# PineapplePi-F1.net
KiCad netlist of a schematic drawn in Altium Designer
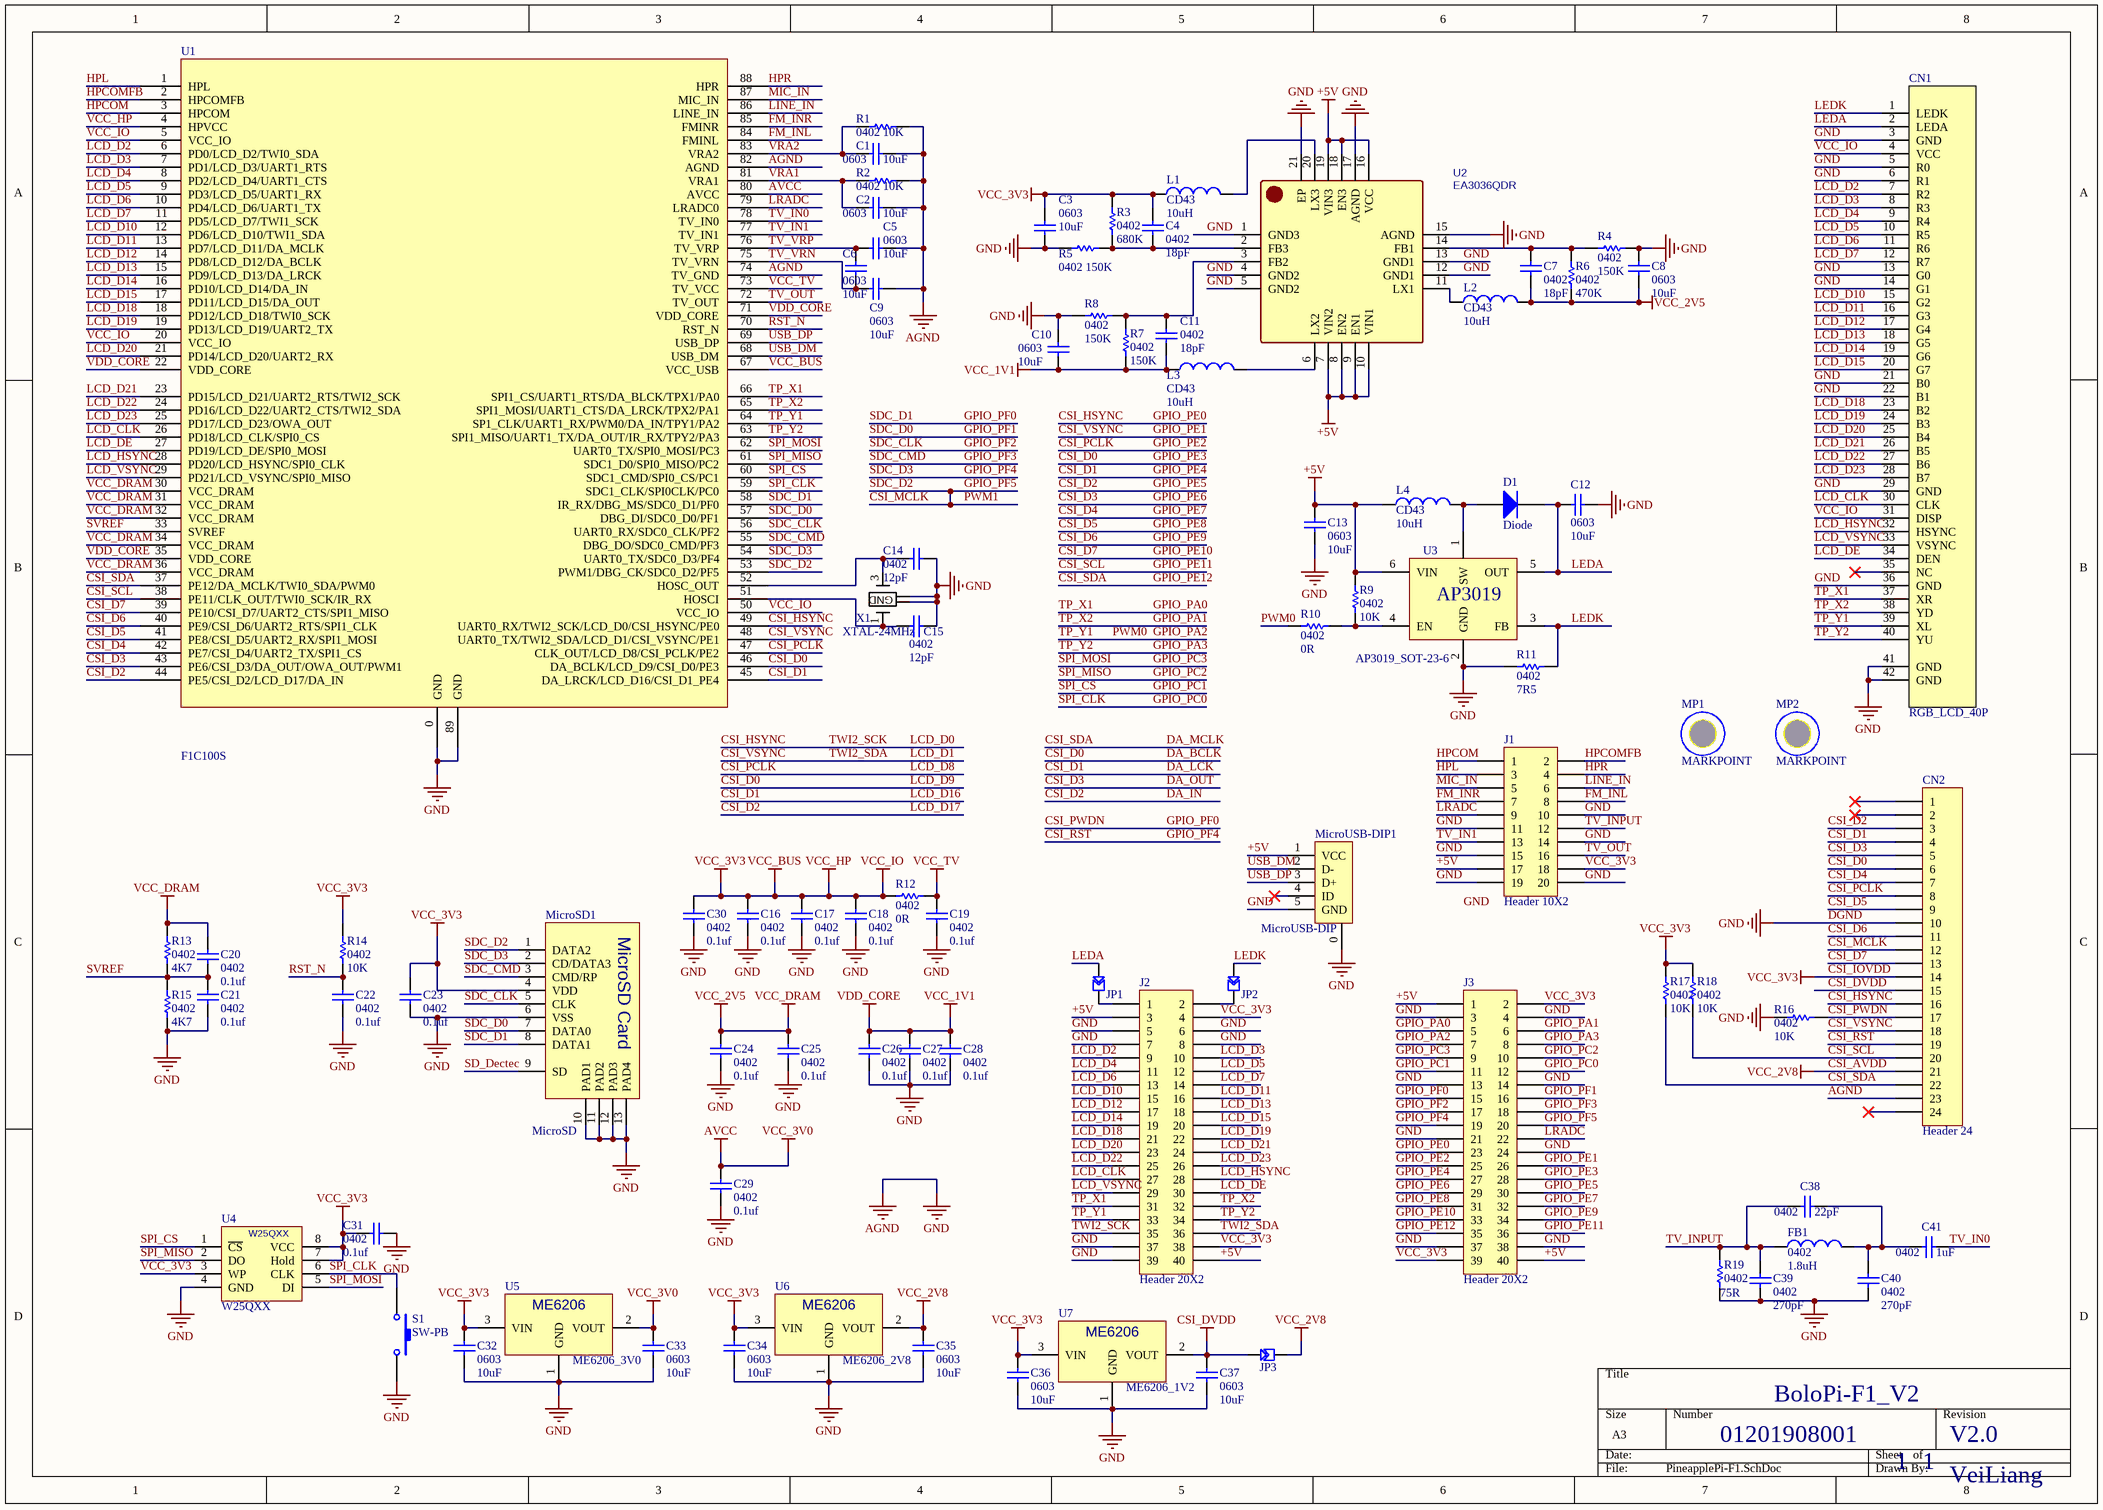
[diagram p0: PineapplePi-F1.SchDoc]

(export (version "E")
  (design (tool "Eeschema 10.0.6"))
  (components
    (comp (ref "C1")
      (value "0603")
      (footprint "0603AC")
      (description "Capacitor")
      (fields (field (name "ALTIUM_VALUE") "10uF") (field (name "PUBLISHER") "Altium Limited"))
      (libsource (lib "Miscellaneous Devices") (part "Cap"))
    )
    (comp (ref "C2")
      (value "0603")
      (footprint "0603AC")
      (description "Capacitor")
      (fields (field (name "ALTIUM_VALUE") "10uF") (field (name "PUBLISHER") "Altium Limited"))
      (libsource (lib "Miscellaneous Devices") (part "Cap"))
    )
    (comp (ref "C3")
      (value "0603")
      (footprint "0603AC")
      (description "Capacitor")
      (fields (field (name "ALTIUM_VALUE") "10uF") (field (name "PUBLISHER") "Altium Limited"))
      (libsource (lib "Miscellaneous Devices") (part "Cap"))
    )
    (comp (ref "C4")
      (value "0402")
      (footprint "0402AC")
      (description "Capacitor")
      (fields (field (name "ALTIUM_VALUE") "18pF") (field (name "PUBLISHER") "Altium Limited"))
      (libsource (lib "Miscellaneous Devices") (part "Cap"))
    )
    (comp (ref "C5")
      (value "0603")
      (footprint "0603AC")
      (description "Capacitor")
      (fields (field (name "ALTIUM_VALUE") "10uF") (field (name "PUBLISHER") "Altium Limited"))
      (libsource (lib "Miscellaneous Devices") (part "Cap"))
    )
    (comp (ref "C6")
      (value "0603")
      (footprint "0603AC")
      (description "Capacitor")
      (fields (field (name "ALTIUM_VALUE") "10uF") (field (name "PUBLISHER") "Altium Limited"))
      (libsource (lib "Miscellaneous Devices") (part "Cap"))
    )
    (comp (ref "C7")
      (value "0402")
      (footprint "0402AC")
      (description "Capacitor")
      (fields (field (name "ALTIUM_VALUE") "18pF") (field (name "PUBLISHER") "Altium Limited"))
      (libsource (lib "Miscellaneous Devices") (part "Cap"))
    )
    (comp (ref "C8")
      (value "0603")
      (footprint "0603AC")
      (description "Capacitor")
      (fields (field (name "ALTIUM_VALUE") "10uF") (field (name "PUBLISHER") "Altium Limited"))
      (libsource (lib "Miscellaneous Devices") (part "Cap"))
    )
    (comp (ref "C9")
      (value "0603")
      (footprint "0603AC")
      (description "Capacitor")
      (fields (field (name "ALTIUM_VALUE") "10uF") (field (name "PUBLISHER") "Altium Limited"))
      (libsource (lib "Miscellaneous Devices") (part "Cap"))
    )
    (comp (ref "C10")
      (value "0603")
      (footprint "0603AC")
      (description "Capacitor")
      (fields (field (name "ALTIUM_VALUE") "10uF") (field (name "PUBLISHER") "Altium Limited"))
      (libsource (lib "Miscellaneous Devices") (part "Cap"))
    )
    (comp (ref "C11")
      (value "0402")
      (footprint "0402AC")
      (description "Capacitor")
      (fields (field (name "ALTIUM_VALUE") "18pF") (field (name "PUBLISHER") "Altium Limited"))
      (libsource (lib "Miscellaneous Devices") (part "Cap"))
    )
    (comp (ref "C12")
      (value "0603")
      (footprint "0603AC")
      (description "Capacitor")
      (fields (field (name "ALTIUM_VALUE") "10uF") (field (name "PUBLISHER") "Altium Limited"))
      (libsource (lib "Miscellaneous Devices") (part "Cap"))
    )
    (comp (ref "C13")
      (value "0603")
      (footprint "0603AC")
      (description "Capacitor")
      (fields (field (name "ALTIUM_VALUE") "10uF") (field (name "PUBLISHER") "Altium Limited"))
      (libsource (lib "Miscellaneous Devices") (part "Cap"))
    )
    (comp (ref "C14")
      (value "0402")
      (footprint "0402AC")
      (description "Capacitor")
      (fields (field (name "ALTIUM_VALUE") "12pF") (field (name "PUBLISHER") "Altium Limited"))
      (libsource (lib "Miscellaneous Devices") (part "Cap"))
    )
    (comp (ref "C15")
      (value "0402")
      (footprint "0402AC")
      (description "Capacitor")
      (fields (field (name "ALTIUM_VALUE") "12pF") (field (name "PUBLISHER") "Altium Limited"))
      (libsource (lib "Miscellaneous Devices") (part "Cap"))
    )
    (comp (ref "C16")
      (value "0402")
      (footprint "0402AC")
      (description "Capacitor")
      (fields (field (name "ALTIUM_VALUE") "0.1uf") (field (name "PUBLISHER") "Altium Limited"))
      (libsource (lib "Miscellaneous Devices") (part "Cap"))
    )
    (comp (ref "C17")
      (value "0402")
      (footprint "0402AC")
      (description "Capacitor")
      (fields (field (name "ALTIUM_VALUE") "0.1uf") (field (name "PUBLISHER") "Altium Limited"))
      (libsource (lib "Miscellaneous Devices") (part "Cap"))
    )
    (comp (ref "C18")
      (value "0402")
      (footprint "0402AC")
      (description "Capacitor")
      (fields (field (name "ALTIUM_VALUE") "0.1uf") (field (name "PUBLISHER") "Altium Limited"))
      (libsource (lib "Miscellaneous Devices") (part "Cap"))
    )
    (comp (ref "C19")
      (value "0402")
      (footprint "0402AC")
      (description "Capacitor")
      (fields (field (name "ALTIUM_VALUE") "0.1uf") (field (name "PUBLISHER") "Altium Limited"))
      (libsource (lib "Miscellaneous Devices") (part "Cap"))
    )
    (comp (ref "C20")
      (value "0402")
      (footprint "0402AC")
      (description "Capacitor")
      (fields (field (name "ALTIUM_VALUE") "0.1uf") (field (name "PUBLISHER") "Altium Limited"))
      (libsource (lib "Miscellaneous Devices") (part "Cap"))
    )
    (comp (ref "C21")
      (value "0402")
      (footprint "0402AC")
      (description "Capacitor")
      (fields (field (name "ALTIUM_VALUE") "0.1uf") (field (name "PUBLISHER") "Altium Limited"))
      (libsource (lib "Miscellaneous Devices") (part "Cap"))
    )
    (comp (ref "C22")
      (value "0402")
      (footprint "0402AC")
      (description "Capacitor")
      (fields (field (name "ALTIUM_VALUE") "0.1uf") (field (name "PUBLISHER") "Altium Limited"))
      (libsource (lib "Miscellaneous Devices") (part "Cap"))
    )
    (comp (ref "C23")
      (value "0402")
      (footprint "0402AC")
      (description "Capacitor")
      (fields (field (name "ALTIUM_VALUE") "0.1uf") (field (name "PUBLISHER") "Altium Limited"))
      (libsource (lib "Miscellaneous Devices") (part "Cap"))
    )
    (comp (ref "C24")
      (value "0402")
      (footprint "0402AC")
      (description "Capacitor")
      (fields (field (name "ALTIUM_VALUE") "0.1uf") (field (name "PUBLISHER") "Altium Limited"))
      (libsource (lib "Miscellaneous Devices") (part "Cap"))
    )
    (comp (ref "C25")
      (value "0402")
      (footprint "0402AC")
      (description "Capacitor")
      (fields (field (name "ALTIUM_VALUE") "0.1uf") (field (name "PUBLISHER") "Altium Limited"))
      (libsource (lib "Miscellaneous Devices") (part "Cap"))
    )
    (comp (ref "C26")
      (value "0402")
      (footprint "0402AC")
      (description "Capacitor")
      (fields (field (name "ALTIUM_VALUE") "0.1uf") (field (name "PUBLISHER") "Altium Limited"))
      (libsource (lib "Miscellaneous Devices") (part "Cap"))
    )
    (comp (ref "C27")
      (value "0402")
      (footprint "0402AC")
      (description "Capacitor")
      (fields (field (name "ALTIUM_VALUE") "0.1uf") (field (name "PUBLISHER") "Altium Limited"))
      (libsource (lib "Miscellaneous Devices") (part "Cap"))
    )
    (comp (ref "C28")
      (value "0402")
      (footprint "0402AC")
      (description "Capacitor")
      (fields (field (name "ALTIUM_VALUE") "0.1uf") (field (name "PUBLISHER") "Altium Limited"))
      (libsource (lib "Miscellaneous Devices") (part "Cap"))
    )
    (comp (ref "C29")
      (value "0402")
      (footprint "0402AC")
      (description "Capacitor")
      (fields (field (name "ALTIUM_VALUE") "0.1uf") (field (name "PUBLISHER") "Altium Limited"))
      (libsource (lib "Miscellaneous Devices") (part "Cap"))
    )
    (comp (ref "C30")
      (value "0402")
      (footprint "0402AC")
      (description "Capacitor")
      (fields (field (name "ALTIUM_VALUE") "0.1uf") (field (name "PUBLISHER") "Altium Limited"))
      (libsource (lib "Miscellaneous Devices") (part "Cap"))
    )
    (comp (ref "C31")
      (value "0402")
      (footprint "0402AC")
      (description "Capacitor")
      (fields (field (name "ALTIUM_VALUE") "0.1uf") (field (name "PUBLISHER") "Altium Limited"))
      (libsource (lib "Miscellaneous Devices") (part "Cap"))
    )
    (comp (ref "C32")
      (value "0603")
      (footprint "0603AC")
      (description "Capacitor")
      (fields (field (name "ALTIUM_VALUE") "10uF") (field (name "PUBLISHER") "Altium Limited"))
      (libsource (lib "Miscellaneous Devices") (part "Cap"))
    )
    (comp (ref "C33")
      (value "0603")
      (footprint "0603AC")
      (description "Capacitor")
      (fields (field (name "ALTIUM_VALUE") "10uF") (field (name "PUBLISHER") "Altium Limited"))
      (libsource (lib "Miscellaneous Devices") (part "Cap"))
    )
    (comp (ref "C34")
      (value "0603")
      (footprint "0603AC")
      (description "Capacitor")
      (fields (field (name "ALTIUM_VALUE") "10uF") (field (name "PUBLISHER") "Altium Limited"))
      (libsource (lib "Miscellaneous Devices") (part "Cap"))
    )
    (comp (ref "C35")
      (value "0603")
      (footprint "0603AC")
      (description "Capacitor")
      (fields (field (name "ALTIUM_VALUE") "10uF") (field (name "PUBLISHER") "Altium Limited"))
      (libsource (lib "Miscellaneous Devices") (part "Cap"))
    )
    (comp (ref "C36")
      (value "0603")
      (footprint "0603AC")
      (description "Capacitor")
      (fields (field (name "ALTIUM_VALUE") "10uF") (field (name "PUBLISHER") "Altium Limited"))
      (libsource (lib "Miscellaneous Devices") (part "Cap"))
    )
    (comp (ref "C37")
      (value "0603")
      (footprint "0603AC")
      (description "Capacitor")
      (fields (field (name "ALTIUM_VALUE") "10uF") (field (name "PUBLISHER") "Altium Limited"))
      (libsource (lib "Miscellaneous Devices") (part "Cap"))
    )
    (comp (ref "C38")
      (value "0402")
      (footprint "0402AC")
      (description "Capacitor")
      (fields (field (name "ALTIUM_VALUE") "22pF") (field (name "PUBLISHER") "Altium Limited"))
      (libsource (lib "Miscellaneous Devices") (part "Cap"))
    )
    (comp (ref "C39")
      (value "0402")
      (footprint "0402AC")
      (description "Capacitor")
      (fields (field (name "ALTIUM_VALUE") "270pF") (field (name "PUBLISHER") "Altium Limited"))
      (libsource (lib "Miscellaneous Devices") (part "Cap"))
    )
    (comp (ref "C40")
      (value "0402")
      (footprint "0402AC")
      (description "Capacitor")
      (fields (field (name "ALTIUM_VALUE") "270pF") (field (name "PUBLISHER") "Altium Limited"))
      (libsource (lib "Miscellaneous Devices") (part "Cap"))
    )
    (comp (ref "C41")
      (value "0402")
      (footprint "0402AC")
      (description "Capacitor")
      (fields (field (name "ALTIUM_VALUE") "1uF") (field (name "PUBLISHER") "Altium Limited"))
      (libsource (lib "Miscellaneous Devices") (part "Cap"))
    )
    (comp (ref "CN1")
      (value "RGB_LCD_40P")
      (footprint "FH19C-40S-0.5SH")
      (libsource (lib "7426SCH") (part "RGB_LCD_40P"))
    )
    (comp (ref "CN2")
      (value "Header 24")
      (footprint "FH19C-24S-0.5SH")
      (description "Header, 24-Pin")
      (fields (field (name "PUBLISHER") "Altium Limited"))
      (libsource (lib "Miscellaneous Connectors") (part "Header 24"))
    )
    (comp (ref "D1")
      (value "Diode")
      (footprint "SOD123")
      (description "Default Diode")
      (fields (field (name "PUBLISHER") "Altium Limited"))
      (libsource (lib "Miscellaneous Devices") (part "Diode"))
    )
    (comp (ref "FB1")
      (value "0402")
      (footprint "0402AR")
      (description "CD43")
      (fields (field (name "ALTIUM_VALUE") "1.8uH") (field (name "PUBLISHER") "Altium Limited"))
      (libsource (lib "Miscellaneous Devices") (part "Inductor"))
    )
    (comp (ref "J1")
      (value "Header 10X2")
      (footprint "Headers:HDR2X10-2.0mm")
      (description "Header, 10-Pin, Dual row")
      (fields (field (name "PUBLISHER") "Altium Limited"))
      (libsource (lib "Miscellaneous Connectors") (part "Header 10X2"))
    )
    (comp (ref "J2")
      (value "Header 20X2")
      (footprint "headers:HDR2X20")
      (description "Header, 20-Pin, Dual row")
      (fields (field (name "PUBLISHER") "Altium Limited"))
      (libsource (lib "Miscellaneous Connectors") (part "Header 20X2"))
    )
    (comp (ref "J3")
      (value "Header 20X2")
      (footprint "headers:HDR2X20")
      (description "Header, 20-Pin, Dual row")
      (fields (field (name "PUBLISHER") "Altium Limited"))
      (libsource (lib "Miscellaneous Connectors") (part "Header 20X2"))
    )
    (comp (ref "JP1") (value "SW-PAD-2") (footprint "SW-PAD-2") (libsource (lib "7426SCH") (part "SW-PAD-2")))
    (comp (ref "JP2") (value "SW-PAD-2") (footprint "SW-PAD-2") (libsource (lib "7426SCH") (part "SW-PAD-2")))
    (comp (ref "JP3") (value "SW-PAD-2") (footprint "SW-PAD-2") (libsource (lib "7426SCH") (part "SW-PAD-2")))
    (comp (ref "L1")
      (value "CD43")
      (footprint "2520")
      (fields (field (name "ALTIUM_VALUE") "10uH") (field (name "PUBLISHER") "Altium Limited"))
      (libsource (lib "Miscellaneous Devices") (part "Inductor"))
    )
    (comp (ref "L2")
      (value "CD43")
      (footprint "2520")
      (fields (field (name "ALTIUM_VALUE") "10uH") (field (name "PUBLISHER") "Altium Limited"))
      (libsource (lib "Miscellaneous Devices") (part "Inductor"))
    )
    (comp (ref "L3")
      (value "CD43")
      (footprint "2520")
      (fields (field (name "ALTIUM_VALUE") "10uH") (field (name "PUBLISHER") "Altium Limited"))
      (libsource (lib "Miscellaneous Devices") (part "Inductor"))
    )
    (comp (ref "L4")
      (value "CD43")
      (footprint "2520")
      (fields (field (name "ALTIUM_VALUE") "10uH") (field (name "PUBLISHER") "Altium Limited"))
      (libsource (lib "Miscellaneous Devices") (part "Inductor"))
    )
    (comp (ref "MicroSD1")
      (value "MicroSD")
      (footprint "MicroSD")
      (libsource (lib "7426SCH") (part "MicroSD"))
    )
    (comp (ref "MicroUSB-DIP1")
      (value "MicroUSB-DIP")
      (footprint "MICRO_USB_DIP")
      (libsource (lib "7426SCH") (part "MicroUSB-DIP"))
    )
    (comp (ref "MP1")
      (value "MARKPOINT")
      (footprint "MARKPOINT")
      (libsource (lib "7426SCH") (part "MARKPOINT"))
    )
    (comp (ref "MP2")
      (value "MARKPOINT")
      (footprint "MARKPOINT")
      (libsource (lib "7426SCH") (part "MARKPOINT"))
    )
    (comp (ref "R1")
      (value "0402")
      (footprint "0402AR")
      (description "Resistor")
      (fields (field (name "ALTIUM_VALUE") "10K") (field (name "PUBLISHER") "Altium Limited"))
      (libsource (lib "Miscellaneous Devices") (part "Res1"))
    )
    (comp (ref "R2")
      (value "0402")
      (footprint "0402AR")
      (description "Resistor")
      (fields (field (name "ALTIUM_VALUE") "10K") (field (name "PUBLISHER") "Altium Limited"))
      (libsource (lib "Miscellaneous Devices") (part "Res1"))
    )
    (comp (ref "R3")
      (value "0402")
      (footprint "0402AR")
      (fields (field (name "ALTIUM_VALUE") "680K") (field (name "PUBLISHER") "Altium Limited"))
      (libsource (lib "Miscellaneous Devices") (part "Res1"))
    )
    (comp (ref "R4")
      (value "0402")
      (footprint "0402AR")
      (description "Resistor")
      (fields (field (name "ALTIUM_VALUE") "150K") (field (name "PUBLISHER") "Altium Limited"))
      (libsource (lib "Miscellaneous Devices") (part "Res1"))
    )
    (comp (ref "R5")
      (value "0402")
      (footprint "0402AR")
      (description "Resistor")
      (fields (field (name "ALTIUM_VALUE") "150K") (field (name "PUBLISHER") "Altium Limited"))
      (libsource (lib "Miscellaneous Devices") (part "Res1"))
    )
    (comp (ref "R6")
      (value "0402")
      (footprint "0402AR")
      (fields (field (name "ALTIUM_VALUE") "470K") (field (name "PUBLISHER") "Altium Limited"))
      (libsource (lib "Miscellaneous Devices") (part "Res1"))
    )
    (comp (ref "R7")
      (value "0402")
      (footprint "0402AR")
      (fields (field (name "ALTIUM_VALUE") "150K") (field (name "PUBLISHER") "Altium Limited"))
      (libsource (lib "Miscellaneous Devices") (part "Res1"))
    )
    (comp (ref "R8")
      (value "0402")
      (footprint "0402AR")
      (fields (field (name "ALTIUM_VALUE") "150K") (field (name "PUBLISHER") "Altium Limited"))
      (libsource (lib "Miscellaneous Devices") (part "Res1"))
    )
    (comp (ref "R9")
      (value "0402")
      (footprint "0402AR")
      (fields (field (name "ALTIUM_VALUE") "10K") (field (name "PUBLISHER") "Altium Limited"))
      (libsource (lib "Miscellaneous Devices") (part "Res1"))
    )
    (comp (ref "R10")
      (value "0402")
      (footprint "0402AR")
      (fields (field (name "ALTIUM_VALUE") "0R") (field (name "PUBLISHER") "Altium Limited"))
      (libsource (lib "Miscellaneous Devices") (part "Res1"))
    )
    (comp (ref "R11")
      (value "0402")
      (footprint "0402AR")
      (fields (field (name "ALTIUM_VALUE") "7R5") (field (name "PUBLISHER") "Altium Limited"))
      (libsource (lib "Miscellaneous Devices") (part "Res1"))
    )
    (comp (ref "R12")
      (value "0402")
      (footprint "0402AR")
      (fields (field (name "ALTIUM_VALUE") "0R") (field (name "PUBLISHER") "Altium Limited"))
      (libsource (lib "Miscellaneous Devices") (part "Res1"))
    )
    (comp (ref "R13")
      (value "0402")
      (footprint "0402AR")
      (fields (field (name "ALTIUM_VALUE") "4K7") (field (name "PUBLISHER") "Altium Limited"))
      (libsource (lib "Miscellaneous Devices") (part "Res1"))
    )
    (comp (ref "R14")
      (value "0402")
      (footprint "0402AR")
      (fields (field (name "ALTIUM_VALUE") "10K") (field (name "PUBLISHER") "Altium Limited"))
      (libsource (lib "Miscellaneous Devices") (part "Res1"))
    )
    (comp (ref "R15")
      (value "0402")
      (footprint "0402AR")
      (fields (field (name "ALTIUM_VALUE") "4K7") (field (name "PUBLISHER") "Altium Limited"))
      (libsource (lib "Miscellaneous Devices") (part "Res1"))
    )
    (comp (ref "R16")
      (value "0402")
      (footprint "0402AR")
      (fields (field (name "ALTIUM_VALUE") "10K") (field (name "PUBLISHER") "Altium Limited"))
      (libsource (lib "Miscellaneous Devices") (part "Res1"))
    )
    (comp (ref "R17")
      (value "0402")
      (footprint "0402AR")
      (fields (field (name "ALTIUM_VALUE") "10K") (field (name "PUBLISHER") "Altium Limited"))
      (libsource (lib "Miscellaneous Devices") (part "Res1"))
    )
    (comp (ref "R18")
      (value "0402")
      (footprint "0402AR")
      (fields (field (name "ALTIUM_VALUE") "10K") (field (name "PUBLISHER") "Altium Limited"))
      (libsource (lib "Miscellaneous Devices") (part "Res1"))
    )
    (comp (ref "R19")
      (value "0402")
      (footprint "0402AR")
      (description "Resistor")
      (fields (field (name "ALTIUM_VALUE") "75R") (field (name "PUBLISHER") "Altium Limited"))
      (libsource (lib "Miscellaneous Devices") (part "Res1"))
    )
    (comp (ref "S1")
      (value "SW-PB")
      (footprint "SW-SMD1")
      (description "Switch")
      (fields (field (name "PUBLISHER") "Altium Limited"))
      (libsource (lib "Miscellaneous Devices") (part "SW-PB"))
    )
    (comp (ref "U1") (value "F1C100S") (footprint "QFN88-10X10") (libsource (lib "7426SCH") (part "F1C100S")))
    (comp (ref "U2")
      (value "EA3036QDR")
      (footprint "QFN20-3x3-0.4")
      (fields (field (name "BOM_SUPPLIER PART") "C111587"))
      (libsource (lib "IC") (part "EA3036QDR"))
    )
    (comp (ref "U3") (value "AP3019_SOT-23-6") (footprint "SOT23-6") (libsource (lib "IC") (part "AP3019")))
    (comp (ref "U4") (value "W25QXX") (footprint "IC:SO-8M") (libsource (lib "IC") (part "W25QXX")))
    (comp (ref "U5") (value "ME6206_3V0") (footprint "SOT-23") (libsource (lib "IC") (part "ME6206")))
    (comp (ref "U6") (value "ME6206_2V8") (footprint "SOT-23") (libsource (lib "IC") (part "ME6206")))
    (comp (ref "U7") (value "ME6206_1V2") (footprint "SOT-23") (libsource (lib "IC") (part "ME6206")))
    (comp (ref "X1")
      (value "XTAL-24MHz")
      (footprint "XTAL-3225")
      (libsource (lib "7426SCH") (part "XTAL-SMD"))
    )
  )
  (nets
    (net (code "1") (name "+5V") (class "Default")
      (node (ref "C13") (pin "2") (pinfunction "2_2") (pintype "passive"))
      (node (ref "J1") (pin "17") (pinfunction "17_17") (pintype "passive"))
      (node (ref "J2") (pin "3") (pinfunction "3_3") (pintype "passive"))
      (node (ref "J2") (pin "40") (pinfunction "40_40") (pintype "passive"))
      (node (ref "J3") (pin "1") (pinfunction "1_1") (pintype "passive"))
      (node (ref "J3") (pin "40") (pinfunction "40_40") (pintype "passive"))
      (node (ref "L4") (pin "1") (pinfunction "1_1") (pintype "passive"))
      (node (ref "MicroUSB-DIP1") (pin "1") (pinfunction "VCC_1") (pintype "power_in"))
      (node (ref "R9") (pin "1") (pinfunction "1_1") (pintype "passive"))
      (node (ref "U2") (pin "10") (pinfunction "VIN1_10") (pintype "passive"))
      (node (ref "U2") (pin "16") (pinfunction "VCC_16") (pintype "passive"))
      (node (ref "U2") (pin "18") (pinfunction "EN3_18") (pintype "passive"))
      (node (ref "U2") (pin "19") (pinfunction "VIN3_19") (pintype "passive"))
      (node (ref "U2") (pin "7") (pinfunction "VIN2_7") (pintype "passive"))
      (node (ref "U2") (pin "8") (pinfunction "EN2_8") (pintype "passive"))
      (node (ref "U2") (pin "9") (pinfunction "EN1_9") (pintype "passive"))
      (node (ref "U3") (pin "6") (pinfunction "VIN_6") (pintype "passive"))
    )
    (net (code "2") (name "/CSI_D0") (class "Default")
      (node (ref "CN2") (pin "6") (pinfunction "6_6") (pintype "passive"))
      (node (ref "J3") (pin "28") (pinfunction "28_28") (pintype "passive"))
      (node (ref "U1") (pin "46") (pinfunction "DA_BCLK/LCD_D9/CSI_D0/PE3_46") (pintype "passive"))
    )
    (net (code "3") (name "/CSI_D1") (class "Default")
      (node (ref "CN2") (pin "4") (pinfunction "4_4") (pintype "passive"))
      (node (ref "J3") (pin "27") (pinfunction "27_27") (pintype "passive"))
      (node (ref "U1") (pin "45") (pinfunction "DA_LRCK/LCD_D16/CSI_D1_PE4_45") (pintype "passive"))
    )
    (net (code "4") (name "/CSI_D2") (class "Default")
      (node (ref "CN2") (pin "3") (pinfunction "3_3") (pintype "passive"))
      (node (ref "J3") (pin "30") (pinfunction "30_30") (pintype "passive"))
      (node (ref "U1") (pin "44") (pinfunction "PE5/CSI_D2/LCD_D17/DA_IN_44") (pintype "passive"))
    )
    (net (code "5") (name "/CSI_D3") (class "Default")
      (node (ref "CN2") (pin "5") (pinfunction "5_5") (pintype "passive"))
      (node (ref "J3") (pin "29") (pinfunction "29_29") (pintype "passive"))
      (node (ref "U1") (pin "43") (pinfunction "PE6/CSI_D3/DA_OUT/OWA_OUT/PWM1_43") (pintype "passive"))
    )
    (net (code "6") (name "/CSI_D4") (class "Default")
      (node (ref "CN2") (pin "7") (pinfunction "7_7") (pintype "passive"))
      (node (ref "J3") (pin "32") (pinfunction "32_32") (pintype "passive"))
      (node (ref "U1") (pin "42") (pinfunction "PE7/CSI_D4/UART2_TX/SPI1_CS_42") (pintype "passive"))
    )
    (net (code "7") (name "/CSI_D5") (class "Default")
      (node (ref "CN2") (pin "9") (pinfunction "9_9") (pintype "passive"))
      (node (ref "J3") (pin "31") (pinfunction "31_31") (pintype "passive"))
      (node (ref "U1") (pin "41") (pinfunction "PE8/CSI_D5/UART2_RX/SPI1_MOSI_41") (pintype "passive"))
    )
    (net (code "8") (name "/CSI_D6") (class "Default")
      (node (ref "CN2") (pin "11") (pinfunction "11_11") (pintype "passive"))
      (node (ref "J3") (pin "34") (pinfunction "34_34") (pintype "passive"))
      (node (ref "U1") (pin "40") (pinfunction "PE9/CSI_D6/UART2_RTS/SPI1_CLK_40") (pintype "passive"))
    )
    (net (code "9") (name "/CSI_D7") (class "Default")
      (node (ref "CN2") (pin "13") (pinfunction "13_13") (pintype "passive"))
      (node (ref "J3") (pin "33") (pinfunction "33_33") (pintype "passive"))
      (node (ref "U1") (pin "39") (pinfunction "PE10/CSI_D7/UART2_CTS/SPI1_MISO_39") (pintype "passive"))
    )
    (net (code "10") (name "/CSI_HSYNC") (class "Default")
      (node (ref "CN2") (pin "16") (pinfunction "16_16") (pintype "passive"))
      (node (ref "J2") (pin "35") (pinfunction "35_35") (pintype "passive"))
      (node (ref "J3") (pin "23") (pinfunction "23_23") (pintype "passive"))
      (node (ref "U1") (pin "49") (pinfunction "UART0_RX/TWI2_SCK/LCD_D0/CSI_HSYNC/PE0_49") (pintype "passive"))
    )
    (net (code "11") (name "/CSI_MCLK") (class "Default")
      (node (ref "CN2") (pin "12") (pinfunction "12_12") (pintype "passive"))
      (node (ref "J3") (pin "20") (pinfunction "20_20") (pintype "passive"))
      (node (ref "MicroSD1") (pin "1") (pinfunction "DATA2_1") (pintype "power_in"))
      (node (ref "U1") (pin "53") (pinfunction "PWM1/DBG_CK/SDC0_D2/PF5_53") (pintype "passive"))
    )
    (net (code "12") (name "/CSI_PCLK") (class "Default")
      (node (ref "CN2") (pin "8") (pinfunction "8_8") (pintype "passive"))
      (node (ref "J3") (pin "25") (pinfunction "25_25") (pintype "passive"))
      (node (ref "U1") (pin "47") (pinfunction "CLK_OUT/LCD_D8/CSI_PCLK/PE2_47") (pintype "passive"))
    )
    (net (code "13") (name "/CSI_PWDN") (class "Default")
      (node (ref "CN2") (pin "17") (pinfunction "17_17") (pintype "passive"))
      (node (ref "J3") (pin "15") (pinfunction "15_15") (pintype "passive"))
      (node (ref "MicroSD1") (pin "8") (pinfunction "DATA1_8") (pintype "power_in"))
      (node (ref "R16") (pin "2") (pinfunction "2_2") (pintype "passive"))
      (node (ref "U1") (pin "58") (pinfunction "IR_RX/DBG_MS/SDC0_D1/PF0_58") (pintype "passive"))
    )
    (net (code "14") (name "/CSI_RST") (class "Default")
      (node (ref "CN2") (pin "19") (pinfunction "19_19") (pintype "passive"))
      (node (ref "J3") (pin "19") (pinfunction "19_19") (pintype "passive"))
      (node (ref "MicroSD1") (pin "2") (pinfunction "CD/DATA3_2") (pintype "power_in"))
      (node (ref "U1") (pin "54") (pinfunction "UART0_TX/SDC0_D3/PF4_54") (pintype "passive"))
    )
    (net (code "15") (name "/CSI_SCL") (class "Default")
      (node (ref "CN2") (pin "20") (pinfunction "20_20") (pintype "passive"))
      (node (ref "J3") (pin "36") (pinfunction "36_36") (pintype "passive"))
      (node (ref "R18") (pin "1") (pinfunction "1_1") (pintype "passive"))
      (node (ref "U1") (pin "38") (pinfunction "PE11/CLK_OUT/TWI0_SCK/IR_RX_38") (pintype "passive"))
    )
    (net (code "16") (name "/CSI_SDA") (class "Default")
      (node (ref "CN2") (pin "22") (pinfunction "22_22") (pintype "passive"))
      (node (ref "J3") (pin "35") (pinfunction "35_35") (pintype "passive"))
      (node (ref "R17") (pin "1") (pinfunction "1_1") (pintype "passive"))
      (node (ref "U1") (pin "37") (pinfunction "PE12/DA_MCLK/TWI0_SDA/PWM0_37") (pintype "passive"))
    )
    (net (code "17") (name "/CSI_VSYNC") (class "Default")
      (node (ref "CN2") (pin "18") (pinfunction "18_18") (pintype "passive"))
      (node (ref "J2") (pin "36") (pinfunction "36_36") (pintype "passive"))
      (node (ref "J3") (pin "26") (pinfunction "26_26") (pintype "passive"))
      (node (ref "U1") (pin "48") (pinfunction "UART0_TX/TWI2_SDA/LCD_D1/CSI_VSYNC/PE1_48") (pintype "passive"))
    )
    (net (code "18") (name "/FM_INL") (class "Default")
      (node (ref "J1") (pin "8") (pinfunction "8_8") (pintype "passive"))
      (node (ref "U1") (pin "84") (pinfunction "FMINL_84") (pintype "passive"))
    )
    (net (code "19") (name "/FM_INR") (class "Default")
      (node (ref "J1") (pin "7") (pinfunction "7_7") (pintype "passive"))
      (node (ref "U1") (pin "85") (pinfunction "FMINR_85") (pintype "passive"))
    )
    (net (code "20") (name "/GPIO_PA0") (class "Default")
      (node (ref "CN1") (pin "37") (pinfunction "XR_37") (pintype "passive"))
      (node (ref "J2") (pin "31") (pinfunction "31_31") (pintype "passive"))
      (node (ref "J3") (pin "5") (pinfunction "5_5") (pintype "passive"))
      (node (ref "U1") (pin "66") (pinfunction "SPI1_CS/UART1_RTS/DA_BLCK/TPX1/PA0_66") (pintype "passive"))
    )
    (net (code "21") (name "/GPIO_PA1") (class "Default")
      (node (ref "CN1") (pin "38") (pinfunction "YD_38") (pintype "passive"))
      (node (ref "J2") (pin "32") (pinfunction "32_32") (pintype "passive"))
      (node (ref "J3") (pin "6") (pinfunction "6_6") (pintype "passive"))
      (node (ref "U1") (pin "65") (pinfunction "SPI1_MOSI/UART1_CTS/DA_LRCK/TPX2/PA1_65") (pintype "passive"))
    )
    (net (code "22") (name "/GPIO_PA2") (class "Default")
      (node (ref "CN1") (pin "39") (pinfunction "XL_39") (pintype "passive"))
      (node (ref "J2") (pin "33") (pinfunction "33_33") (pintype "passive"))
      (node (ref "J3") (pin "7") (pinfunction "7_7") (pintype "passive"))
      (node (ref "R10") (pin "1") (pinfunction "1_1") (pintype "passive"))
      (node (ref "U1") (pin "64") (pinfunction "SP1_CLK/UART1_RX/PWM0/DA_IN/TPY1/PA2_64") (pintype "passive"))
    )
    (net (code "23") (name "/GPIO_PA3") (class "Default")
      (node (ref "CN1") (pin "40") (pinfunction "YU_40") (pintype "passive"))
      (node (ref "J2") (pin "34") (pinfunction "34_34") (pintype "passive"))
      (node (ref "J3") (pin "8") (pinfunction "8_8") (pintype "passive"))
      (node (ref "U1") (pin "63") (pinfunction "SPI1_MISO/UART1_TX/DA_OUT/IR_RX/TPY2/PA3_63") (pintype "passive"))
    )
    (net (code "24") (name "/GPIO_PC0") (class "Default")
      (node (ref "J3") (pin "12") (pinfunction "12_12") (pintype "passive"))
      (node (ref "S1") (pin "1") (pinfunction "1_1") (pintype "passive"))
      (node (ref "U1") (pin "59") (pinfunction "SDC1_CLK/SPI0CLK/PC0_59") (pintype "passive"))
      (node (ref "U4") (pin "6") (pinfunction "CLK_6") (pintype "power_in"))
    )
    (net (code "25") (name "/GPIO_PC1") (class "Default")
      (node (ref "J3") (pin "11") (pinfunction "11_11") (pintype "passive"))
      (node (ref "U1") (pin "60") (pinfunction "SDC1_CMD/SPI0_CS/PC1_60") (pintype "passive"))
      (node (ref "U4") (pin "1") (pinfunction "~{CS}_1") (pintype "power_in"))
    )
    (net (code "26") (name "/GPIO_PC2") (class "Default")
      (node (ref "J3") (pin "10") (pinfunction "10_10") (pintype "passive"))
      (node (ref "U1") (pin "61") (pinfunction "SDC1_D0/SPI0_MISO/PC2_61") (pintype "passive"))
      (node (ref "U4") (pin "2") (pinfunction "DO_2") (pintype "power_in"))
    )
    (net (code "27") (name "/GPIO_PC3") (class "Default")
      (node (ref "J3") (pin "9") (pinfunction "9_9") (pintype "passive"))
      (node (ref "U1") (pin "62") (pinfunction "UART0_TX/SPI0_MOSI/PC3_62") (pintype "passive"))
      (node (ref "U4") (pin "5") (pinfunction "DI_5") (pintype "power_in"))
    )
    (net (code "28") (name "/GPIO_PF1") (class "Default")
      (node (ref "J3") (pin "16") (pinfunction "16_16") (pintype "passive"))
      (node (ref "MicroSD1") (pin "7") (pinfunction "DATA0_7") (pintype "power_in"))
      (node (ref "U1") (pin "57") (pinfunction "DBG_DI/SDC0_D0/PF1_57") (pintype "passive"))
    )
    (net (code "29") (name "/GPIO_PF2") (class "Default")
      (node (ref "J3") (pin "17") (pinfunction "17_17") (pintype "passive"))
      (node (ref "MicroSD1") (pin "5") (pinfunction "CLK_5") (pintype "power_in"))
      (node (ref "U1") (pin "56") (pinfunction "UART0_RX/SDC0_CLK/PF2_56") (pintype "passive"))
    )
    (net (code "30") (name "/GPIO_PF3") (class "Default")
      (node (ref "J3") (pin "18") (pinfunction "18_18") (pintype "passive"))
      (node (ref "MicroSD1") (pin "3") (pinfunction "CMD/RP_3") (pintype "power_in"))
      (node (ref "U1") (pin "55") (pinfunction "DBG_DO/SDC0_CMD/PF3_55") (pintype "passive"))
    )
    (net (code "31") (name "/HPCOM") (class "Default")
      (node (ref "J1") (pin "1") (pinfunction "1_1") (pintype "passive"))
      (node (ref "U1") (pin "3") (pinfunction "HPCOM_3") (pintype "passive"))
    )
    (net (code "32") (name "/HPCOMFB") (class "Default")
      (node (ref "J1") (pin "2") (pinfunction "2_2") (pintype "passive"))
      (node (ref "U1") (pin "2") (pinfunction "HPCOMFB_2") (pintype "passive"))
    )
    (net (code "33") (name "/HPL") (class "Default")
      (node (ref "J1") (pin "3") (pinfunction "3_3") (pintype "passive"))
      (node (ref "U1") (pin "1") (pinfunction "HPL_1") (pintype "passive"))
    )
    (net (code "34") (name "/HPR") (class "Default")
      (node (ref "J1") (pin "4") (pinfunction "4_4") (pintype "passive"))
      (node (ref "U1") (pin "88") (pinfunction "HPR_88") (pintype "passive"))
    )
    (net (code "35") (name "/LCD_CLK") (class "Default")
      (node (ref "CN1") (pin "30") (pinfunction "CLK_30") (pintype "passive"))
      (node (ref "J2") (pin "27") (pinfunction "27_27") (pintype "passive"))
      (node (ref "U1") (pin "26") (pinfunction "PD18/LCD_CLK/SPI0_CS_26") (pintype "passive"))
    )
    (net (code "36") (name "/LCD_D2") (class "Default")
      (node (ref "CN1") (pin "7") (pinfunction "R2_7") (pintype "passive"))
      (node (ref "J2") (pin "9") (pinfunction "9_9") (pintype "passive"))
      (node (ref "U1") (pin "6") (pinfunction "PD0/LCD_D2/TWI0_SDA_6") (pintype "passive"))
    )
    (net (code "37") (name "/LCD_D3") (class "Default")
      (node (ref "CN1") (pin "8") (pinfunction "R3_8") (pintype "passive"))
      (node (ref "J2") (pin "10") (pinfunction "10_10") (pintype "passive"))
      (node (ref "U1") (pin "7") (pinfunction "PD1/LCD_D3/UART1_RTS_7") (pintype "passive"))
    )
    (net (code "38") (name "/LCD_D4") (class "Default")
      (node (ref "CN1") (pin "9") (pinfunction "R4_9") (pintype "passive"))
      (node (ref "J2") (pin "11") (pinfunction "11_11") (pintype "passive"))
      (node (ref "U1") (pin "8") (pinfunction "PD2/LCD_D4/UART1_CTS_8") (pintype "passive"))
    )
    (net (code "39") (name "/LCD_D5") (class "Default")
      (node (ref "CN1") (pin "10") (pinfunction "R5_10") (pintype "passive"))
      (node (ref "J2") (pin "12") (pinfunction "12_12") (pintype "passive"))
      (node (ref "U1") (pin "9") (pinfunction "PD3/LCD_D5/UART1_RX_9") (pintype "passive"))
    )
    (net (code "40") (name "/LCD_D6") (class "Default")
      (node (ref "CN1") (pin "11") (pinfunction "R6_11") (pintype "passive"))
      (node (ref "J2") (pin "13") (pinfunction "13_13") (pintype "passive"))
      (node (ref "U1") (pin "10") (pinfunction "PD4/LCD_D6/UART1_TX_10") (pintype "passive"))
    )
    (net (code "41") (name "/LCD_D7") (class "Default")
      (node (ref "CN1") (pin "12") (pinfunction "R7_12") (pintype "passive"))
      (node (ref "J2") (pin "14") (pinfunction "14_14") (pintype "passive"))
      (node (ref "U1") (pin "11") (pinfunction "PD5/LCD_D7/TWI1_SCK_11") (pintype "passive"))
    )
    (net (code "42") (name "/LCD_D10") (class "Default")
      (node (ref "CN1") (pin "15") (pinfunction "G2_15") (pintype "passive"))
      (node (ref "J2") (pin "15") (pinfunction "15_15") (pintype "passive"))
      (node (ref "U1") (pin "12") (pinfunction "PD6/LCD_D10/TWI1_SDA_12") (pintype "passive"))
    )
    (net (code "43") (name "/LCD_D11") (class "Default")
      (node (ref "CN1") (pin "16") (pinfunction "G3_16") (pintype "passive"))
      (node (ref "J2") (pin "16") (pinfunction "16_16") (pintype "passive"))
      (node (ref "U1") (pin "13") (pinfunction "PD7/LCD_D11/DA_MCLK_13") (pintype "passive"))
    )
    (net (code "44") (name "/LCD_D12") (class "Default")
      (node (ref "CN1") (pin "17") (pinfunction "G4_17") (pintype "passive"))
      (node (ref "J2") (pin "17") (pinfunction "17_17") (pintype "passive"))
      (node (ref "U1") (pin "14") (pinfunction "PD8/LCD_D12/DA_BCLK_14") (pintype "passive"))
    )
    (net (code "45") (name "/LCD_D13") (class "Default")
      (node (ref "CN1") (pin "18") (pinfunction "G5_18") (pintype "passive"))
      (node (ref "J2") (pin "18") (pinfunction "18_18") (pintype "passive"))
      (node (ref "U1") (pin "15") (pinfunction "PD9/LCD_D13/DA_LRCK_15") (pintype "passive"))
    )
    (net (code "46") (name "/LCD_D14") (class "Default")
      (node (ref "CN1") (pin "19") (pinfunction "G6_19") (pintype "passive"))
      (node (ref "J2") (pin "19") (pinfunction "19_19") (pintype "passive"))
      (node (ref "U1") (pin "16") (pinfunction "PD10/LCD_D14/DA_IN_16") (pintype "passive"))
    )
    (net (code "47") (name "/LCD_D15") (class "Default")
      (node (ref "CN1") (pin "20") (pinfunction "G7_20") (pintype "passive"))
      (node (ref "J2") (pin "20") (pinfunction "20_20") (pintype "passive"))
      (node (ref "U1") (pin "17") (pinfunction "PD11/LCD_D15/DA_OUT_17") (pintype "passive"))
    )
    (net (code "48") (name "/LCD_D18") (class "Default")
      (node (ref "CN1") (pin "23") (pinfunction "B2_23") (pintype "passive"))
      (node (ref "J2") (pin "21") (pinfunction "21_21") (pintype "passive"))
      (node (ref "U1") (pin "18") (pinfunction "PD12/LCD_D18/TWI0_SCK_18") (pintype "passive"))
    )
    (net (code "49") (name "/LCD_D19") (class "Default")
      (node (ref "CN1") (pin "24") (pinfunction "B3_24") (pintype "passive"))
      (node (ref "J2") (pin "22") (pinfunction "22_22") (pintype "passive"))
      (node (ref "U1") (pin "19") (pinfunction "PD13/LCD_D19/UART2_TX_19") (pintype "passive"))
    )
    (net (code "50") (name "/LCD_D20") (class "Default")
      (node (ref "CN1") (pin "25") (pinfunction "B4_25") (pintype "passive"))
      (node (ref "J2") (pin "23") (pinfunction "23_23") (pintype "passive"))
      (node (ref "U1") (pin "21") (pinfunction "PD14/LCD_D20/UART2_RX_21") (pintype "passive"))
    )
    (net (code "51") (name "/LCD_D21") (class "Default")
      (node (ref "CN1") (pin "26") (pinfunction "B5_26") (pintype "passive"))
      (node (ref "J2") (pin "24") (pinfunction "24_24") (pintype "passive"))
      (node (ref "U1") (pin "23") (pinfunction "PD15/LCD_D21/UART2_RTS/TWI2_SCK_23") (pintype "passive"))
    )
    (net (code "52") (name "/LCD_D22") (class "Default")
      (node (ref "CN1") (pin "27") (pinfunction "B6_27") (pintype "passive"))
      (node (ref "J2") (pin "25") (pinfunction "25_25") (pintype "passive"))
      (node (ref "U1") (pin "24") (pinfunction "PD16/LCD_D22/UART2_CTS/TWI2_SDA_24") (pintype "passive"))
    )
    (net (code "53") (name "/LCD_D23") (class "Default")
      (node (ref "CN1") (pin "28") (pinfunction "B7_28") (pintype "passive"))
      (node (ref "J2") (pin "26") (pinfunction "26_26") (pintype "passive"))
      (node (ref "U1") (pin "25") (pinfunction "PD17/LCD_D23/OWA_OUT_25") (pintype "passive"))
    )
    (net (code "54") (name "/LCD_DE") (class "Default")
      (node (ref "CN1") (pin "34") (pinfunction "DEN_34") (pintype "passive"))
      (node (ref "J2") (pin "30") (pinfunction "30_30") (pintype "passive"))
      (node (ref "U1") (pin "27") (pinfunction "PD19/LCD_DE/SPI0_MOSI_27") (pintype "passive"))
    )
    (net (code "55") (name "/LCD_HSYNC") (class "Default")
      (node (ref "CN1") (pin "32") (pinfunction "HSYNC_32") (pintype "passive"))
      (node (ref "J2") (pin "28") (pinfunction "28_28") (pintype "passive"))
      (node (ref "U1") (pin "28") (pinfunction "PD20/LCD_HSYNC/SPI0_CLK_28") (pintype "passive"))
    )
    (net (code "56") (name "/LCD_VSYNC") (class "Default")
      (node (ref "CN1") (pin "33") (pinfunction "VSYNC_33") (pintype "passive"))
      (node (ref "J2") (pin "29") (pinfunction "29_29") (pintype "passive"))
      (node (ref "U1") (pin "29") (pinfunction "PD21/LCD_VSYNC/SPI0_MISO_29") (pintype "passive"))
    )
    (net (code "57") (name "/LEDA") (class "Default")
      (node (ref "C12") (pin "1") (pinfunction "1_1") (pintype "passive"))
      (node (ref "CN1") (pin "2") (pinfunction "LEDA_2") (pintype "passive"))
      (node (ref "D1") (pin "2") (pinfunction "K_2") (pintype "passive"))
      (node (ref "JP1") (pin "1") (pintype "power_in"))
      (node (ref "U3") (pin "5") (pinfunction "OUT_5") (pintype "passive"))
    )
    (net (code "58") (name "/LEDK") (class "Default")
      (node (ref "CN1") (pin "1") (pinfunction "LEDK_1") (pintype "passive"))
      (node (ref "JP2") (pin "1") (pintype "power_in"))
      (node (ref "R11") (pin "2") (pinfunction "2_2") (pintype "passive"))
      (node (ref "U3") (pin "3") (pinfunction "FB_3") (pintype "passive"))
    )
    (net (code "59") (name "/LINE_IN") (class "Default")
      (node (ref "J1") (pin "6") (pinfunction "6_6") (pintype "passive"))
      (node (ref "U1") (pin "86") (pinfunction "LINE_IN_86") (pintype "passive"))
    )
    (net (code "60") (name "/LRADC") (class "Default")
      (node (ref "J1") (pin "9") (pinfunction "9_9") (pintype "passive"))
      (node (ref "J3") (pin "22") (pinfunction "22_22") (pintype "passive"))
      (node (ref "U1") (pin "79") (pinfunction "LRADC0_79") (pintype "passive"))
    )
    (net (code "61") (name "/MIC_IN") (class "Default")
      (node (ref "J1") (pin "5") (pinfunction "5_5") (pintype "passive"))
      (node (ref "U1") (pin "87") (pinfunction "MIC_IN_87") (pintype "passive"))
    )
    (net (code "62") (name "/RST_N") (class "Default")
      (node (ref "C22") (pin "2") (pinfunction "2_2") (pintype "passive"))
      (node (ref "R14") (pin "1") (pinfunction "1_1") (pintype "passive"))
      (node (ref "U1") (pin "70") (pinfunction "RST_N_70") (pintype "passive"))
    )
    (net (code "63") (name "/SD_Dectec") (class "Default")
      (node (ref "MicroSD1") (pin "9") (pinfunction "SD_9") (pintype "power_in"))
    )
    (net (code "64") (name "/SVREF") (class "Default")
      (node (ref "C20") (pin "1") (pinfunction "1_1") (pintype "passive"))
      (node (ref "C21") (pin "2") (pinfunction "2_2") (pintype "passive"))
      (node (ref "R13") (pin "1") (pinfunction "1_1") (pintype "passive"))
      (node (ref "R15") (pin "2") (pinfunction "2_2") (pintype "passive"))
      (node (ref "U1") (pin "33") (pinfunction "SVREF_33") (pintype "passive"))
    )
    (net (code "65") (name "/TV_IN0") (class "Default")
      (node (ref "C41") (pin "1") (pinfunction "1_1") (pintype "passive"))
      (node (ref "U1") (pin "78") (pinfunction "TV_IN0_78") (pintype "passive"))
    )
    (net (code "66") (name "/TV_IN1") (class "Default")
      (node (ref "J1") (pin "13") (pinfunction "13_13") (pintype "passive"))
      (node (ref "U1") (pin "77") (pinfunction "TV_IN1_77") (pintype "passive"))
    )
    (net (code "67") (name "/TV_INPUT") (class "Default")
      (node (ref "C38") (pin "2") (pinfunction "2_2") (pintype "passive"))
      (node (ref "C39") (pin "1") (pinfunction "1_1") (pintype "passive"))
      (node (ref "FB1") (pin "1") (pinfunction "1_1") (pintype "passive"))
      (node (ref "J1") (pin "12") (pinfunction "12_12") (pintype "passive"))
      (node (ref "R19") (pin "2") (pinfunction "2_2") (pintype "passive"))
    )
    (net (code "68") (name "/TV_OUT") (class "Default")
      (node (ref "J1") (pin "16") (pinfunction "16_16") (pintype "passive"))
      (node (ref "U1") (pin "72") (pinfunction "TV_OUT_72") (pintype "passive"))
    )
    (net (code "69") (name "/TV_VRN") (class "Default")
      (node (ref "C6") (pin "1") (pinfunction "1_1") (pintype "passive"))
      (node (ref "C9") (pin "1") (pinfunction "1_1") (pintype "passive"))
      (node (ref "U1") (pin "75") (pinfunction "TV_VRN_75") (pintype "passive"))
    )
    (net (code "70") (name "/TV_VRP") (class "Default")
      (node (ref "C5") (pin "1") (pinfunction "1_1") (pintype "passive"))
      (node (ref "C6") (pin "2") (pinfunction "2_2") (pintype "passive"))
      (node (ref "U1") (pin "76") (pinfunction "TV_VRP_76") (pintype "passive"))
    )
    (net (code "71") (name "/USB_DM") (class "Default")
      (node (ref "MicroUSB-DIP1") (pin "2") (pinfunction "D-_2") (pintype "power_in"))
      (node (ref "U1") (pin "68") (pinfunction "USB_DM_68") (pintype "passive"))
    )
    (net (code "72") (name "/USB_DP") (class "Default")
      (node (ref "MicroUSB-DIP1") (pin "3") (pinfunction "D+_3") (pintype "power_in"))
      (node (ref "U1") (pin "69") (pinfunction "USB_DP_69") (pintype "passive"))
    )
    (net (code "73") (name "/VRA1") (class "Default")
      (node (ref "C2") (pin "1") (pinfunction "1_1") (pintype "passive"))
      (node (ref "R2") (pin "2") (pinfunction "2_2") (pintype "passive"))
      (node (ref "U1") (pin "81") (pinfunction "VRA1_81") (pintype "passive"))
    )
    (net (code "74") (name "/VRA2") (class "Default")
      (node (ref "C1") (pin "1") (pinfunction "1_1") (pintype "passive"))
      (node (ref "R1") (pin "2") (pinfunction "2_2") (pintype "passive"))
      (node (ref "U1") (pin "83") (pinfunction "VRA2_83") (pintype "passive"))
    )
    (net (code "75") (name "AGND") (class "Default")
      (node (ref "C1") (pin "2") (pinfunction "2_2") (pintype "passive"))
      (node (ref "C10") (pin "1") (pinfunction "1_1") (pintype "passive"))
      (node (ref "C12") (pin "2") (pinfunction "2_2") (pintype "passive"))
      (node (ref "C13") (pin "1") (pinfunction "1_1") (pintype "passive"))
      (node (ref "C14") (pin "1") (pinfunction "1_1") (pintype "passive"))
      (node (ref "C15") (pin "1") (pinfunction "1_1") (pintype "passive"))
      (node (ref "C16") (pin "1") (pinfunction "1_1") (pintype "passive"))
      (node (ref "C17") (pin "1") (pinfunction "1_1") (pintype "passive"))
      (node (ref "C18") (pin "1") (pinfunction "1_1") (pintype "passive"))
      (node (ref "C19") (pin "1") (pinfunction "1_1") (pintype "passive"))
      (node (ref "C2") (pin "2") (pinfunction "2_2") (pintype "passive"))
      (node (ref "C21") (pin "1") (pinfunction "1_1") (pintype "passive"))
      (node (ref "C22") (pin "1") (pinfunction "1_1") (pintype "passive"))
      (node (ref "C23") (pin "1") (pinfunction "1_1") (pintype "passive"))
      (node (ref "C24") (pin "1") (pinfunction "1_1") (pintype "passive"))
      (node (ref "C25") (pin "1") (pinfunction "1_1") (pintype "passive"))
      (node (ref "C26") (pin "1") (pinfunction "1_1") (pintype "passive"))
      (node (ref "C27") (pin "1") (pinfunction "1_1") (pintype "passive"))
      (node (ref "C28") (pin "1") (pinfunction "1_1") (pintype "passive"))
      (node (ref "C29") (pin "1") (pinfunction "1_1") (pintype "passive"))
      (node (ref "C3") (pin "2") (pinfunction "2_2") (pintype "passive"))
      (node (ref "C30") (pin "2") (pinfunction "2_2") (pintype "passive"))
      (node (ref "C31") (pin "1") (pinfunction "1_1") (pintype "passive"))
      (node (ref "C32") (pin "1") (pinfunction "1_1") (pintype "passive"))
      (node (ref "C33") (pin "1") (pinfunction "1_1") (pintype "passive"))
      (node (ref "C34") (pin "1") (pinfunction "1_1") (pintype "passive"))
      (node (ref "C35") (pin "1") (pinfunction "1_1") (pintype "passive"))
      (node (ref "C36") (pin "1") (pinfunction "1_1") (pintype "passive"))
      (node (ref "C37") (pin "1") (pinfunction "1_1") (pintype "passive"))
      (node (ref "C39") (pin "2") (pinfunction "2_2") (pintype "passive"))
      (node (ref "C40") (pin "2") (pinfunction "2_2") (pintype "passive"))
      (node (ref "C5") (pin "2") (pinfunction "2_2") (pintype "passive"))
      (node (ref "C8") (pin "2") (pinfunction "2_2") (pintype "passive"))
      (node (ref "C9") (pin "2") (pinfunction "2_2") (pintype "passive"))
      (node (ref "CN1") (pin "13") (pinfunction "G0_13") (pintype "passive"))
      (node (ref "CN1") (pin "14") (pinfunction "G1_14") (pintype "passive"))
      (node (ref "CN1") (pin "21") (pinfunction "B0_21") (pintype "passive"))
      (node (ref "CN1") (pin "22") (pinfunction "B1_22") (pintype "passive"))
      (node (ref "CN1") (pin "29") (pinfunction "GND_29") (pintype "passive"))
      (node (ref "CN1") (pin "3") (pinfunction "GND_3") (pintype "passive"))
      (node (ref "CN1") (pin "36") (pinfunction "GND_36") (pintype "passive"))
      (node (ref "CN1") (pin "41") (pinfunction "GND_41") (pintype "passive"))
      (node (ref "CN1") (pin "42") (pinfunction "GND_42") (pintype "passive"))
      (node (ref "CN1") (pin "5") (pinfunction "R0_5") (pintype "passive"))
      (node (ref "CN1") (pin "6") (pinfunction "R1_6") (pintype "passive"))
      (node (ref "CN2") (pin "10") (pinfunction "10_10") (pintype "passive"))
      (node (ref "CN2") (pin "23") (pinfunction "23_23") (pintype "passive"))
      (node (ref "J1") (pin "10") (pinfunction "10_10") (pintype "passive"))
      (node (ref "J1") (pin "11") (pinfunction "11_11") (pintype "passive"))
      (node (ref "J1") (pin "14") (pinfunction "14_14") (pintype "passive"))
      (node (ref "J1") (pin "15") (pinfunction "15_15") (pintype "passive"))
      (node (ref "J1") (pin "19") (pinfunction "19_19") (pintype "passive"))
      (node (ref "J1") (pin "20") (pinfunction "20_20") (pintype "passive"))
      (node (ref "J2") (pin "37") (pinfunction "37_37") (pintype "passive"))
      (node (ref "J2") (pin "39") (pinfunction "39_39") (pintype "passive"))
      (node (ref "J2") (pin "5") (pinfunction "5_5") (pintype "passive"))
      (node (ref "J2") (pin "6") (pinfunction "6_6") (pintype "passive"))
      (node (ref "J2") (pin "7") (pinfunction "7_7") (pintype "passive"))
      (node (ref "J2") (pin "8") (pinfunction "8_8") (pintype "passive"))
      (node (ref "J3") (pin "13") (pinfunction "13_13") (pintype "passive"))
      (node (ref "J3") (pin "14") (pinfunction "14_14") (pintype "passive"))
      (node (ref "J3") (pin "21") (pinfunction "21_21") (pintype "passive"))
      (node (ref "J3") (pin "24") (pinfunction "24_24") (pintype "passive"))
      (node (ref "J3") (pin "3") (pinfunction "3_3") (pintype "passive"))
      (node (ref "J3") (pin "37") (pinfunction "37_37") (pintype "passive"))
      (node (ref "J3") (pin "38") (pinfunction "38_38") (pintype "passive"))
      (node (ref "J3") (pin "4") (pinfunction "4_4") (pintype "passive"))
      (node (ref "MicroSD1") (pin "10") (pinfunction "PAD1_10") (pintype "power_in"))
      (node (ref "MicroSD1") (pin "11") (pinfunction "PAD2_11") (pintype "power_in"))
      (node (ref "MicroSD1") (pin "12") (pinfunction "PAD3_12") (pintype "power_in"))
      (node (ref "MicroSD1") (pin "13") (pinfunction "PAD4_13") (pintype "power_in"))
      (node (ref "MicroSD1") (pin "6") (pinfunction "VSS_6") (pintype "power_in"))
      (node (ref "MicroUSB-DIP1") (pin "0") (pintype "passive"))
      (node (ref "MicroUSB-DIP1") (pin "5") (pinfunction "GND_5") (pintype "power_in"))
      (node (ref "R1") (pin "1") (pinfunction "1_1") (pintype "passive"))
      (node (ref "R11") (pin "1") (pinfunction "1_1") (pintype "passive"))
      (node (ref "R15") (pin "1") (pinfunction "1_1") (pintype "passive"))
      (node (ref "R16") (pin "1") (pinfunction "1_1") (pintype "passive"))
      (node (ref "R19") (pin "1") (pinfunction "1_1") (pintype "passive"))
      (node (ref "R2") (pin "1") (pinfunction "1_1") (pintype "passive"))
      (node (ref "R4") (pin "2") (pinfunction "2_2") (pintype "passive"))
      (node (ref "R5") (pin "2") (pinfunction "2_2") (pintype "passive"))
      (node (ref "R8") (pin "2") (pinfunction "2_2") (pintype "passive"))
      (node (ref "S1") (pin "2") (pinfunction "2_2") (pintype "passive"))
      (node (ref "U1") (pin "0") (pinfunction "GND_0") (pintype "passive"))
      (node (ref "U1") (pin "74") (pinfunction "TV_GND_74") (pintype "passive"))
      (node (ref "U1") (pin "82") (pinfunction "AGND_82") (pintype "passive"))
      (node (ref "U1") (pin "89") (pinfunction "GND_89") (pintype "passive"))
      (node (ref "U2") (pin "1") (pinfunction "GND3_1") (pintype "passive"))
      (node (ref "U2") (pin "12") (pinfunction "GND1_12") (pintype "passive"))
      (node (ref "U2") (pin "13") (pinfunction "GND1_13") (pintype "passive"))
      (node (ref "U2") (pin "15") (pinfunction "AGND_15") (pintype "passive"))
      (node (ref "U2") (pin "17") (pinfunction "AGND_17") (pintype "passive"))
      (node (ref "U2") (pin "21") (pinfunction "EP_21") (pintype "passive"))
      (node (ref "U2") (pin "4") (pinfunction "GND2_4") (pintype "passive"))
      (node (ref "U2") (pin "5") (pinfunction "GND2_5") (pintype "passive"))
      (node (ref "U3") (pin "2") (pinfunction "GND_2") (pintype "passive"))
      (node (ref "U4") (pin "4") (pinfunction "GND_4") (pintype "power_in"))
      (node (ref "U5") (pin "1") (pinfunction "GND_1") (pintype "power_in"))
      (node (ref "U6") (pin "1") (pinfunction "GND_1") (pintype "power_in"))
      (node (ref "U7") (pin "1") (pinfunction "GND_1") (pintype "power_in"))
      (node (ref "X1") (pin "2") (pintype "power_in"))
      (node (ref "X1") (pin "4") (pintype "passive"))
    )
    (net (code "76") (name "AVCC") (class "Default")
      (node (ref "C29") (pin "2") (pinfunction "2_2") (pintype "passive"))
      (node (ref "C33") (pin "2") (pinfunction "2_2") (pintype "passive"))
      (node (ref "U1") (pin "80") (pinfunction "AVCC_80") (pintype "passive"))
      (node (ref "U5") (pin "2") (pinfunction "VOUT_2") (pintype "power_in"))
    )
    (net (code "77") (name "CSI_DVDD") (class "Default")
      (node (ref "C37") (pin "2") (pinfunction "2_2") (pintype "passive"))
      (node (ref "CN2") (pin "15") (pinfunction "15_15") (pintype "passive"))
      (node (ref "JP3") (pin "1") (pintype "power_in"))
      (node (ref "U7") (pin "2") (pinfunction "VOUT_2") (pintype "power_in"))
    )
    (net (code "78") (name "Net-(C38-Pad1)") (class "Default")
      (node (ref "C38") (pin "1") (pinfunction "1_1") (pintype "passive"))
      (node (ref "C40") (pin "1") (pinfunction "1_1") (pintype "passive"))
      (node (ref "C41") (pin "2") (pinfunction "2_2") (pintype "passive"))
      (node (ref "FB1") (pin "2") (pinfunction "2_2") (pintype "passive"))
    )
    (net (code "79") (name "Net-(D1-A)") (class "Default")
      (node (ref "D1") (pin "1") (pinfunction "A_1") (pintype "passive"))
      (node (ref "L4") (pin "2") (pinfunction "2_2") (pintype "passive"))
      (node (ref "U3") (pin "1") (pinfunction "SW_1") (pintype "passive"))
    )
    (net (code "80") (name "Net-(J2-Pad1)") (class "Default")
      (node (ref "J2") (pin "1") (pinfunction "1_1") (pintype "passive"))
      (node (ref "JP1") (pin "2") (pintype "power_in"))
    )
    (net (code "81") (name "Net-(J2-Pad2)") (class "Default")
      (node (ref "J2") (pin "2") (pinfunction "2_2") (pintype "passive"))
      (node (ref "JP2") (pin "2") (pintype "power_in"))
    )
    (net (code "82") (name "Net-(U1-HOSCI)") (class "Default")
      (node (ref "C15") (pin "2") (pinfunction "2_2") (pintype "passive"))
      (node (ref "U1") (pin "51") (pinfunction "HOSCI_51") (pintype "passive"))
      (node (ref "X1") (pin "1") (pintype "power_in"))
    )
    (net (code "83") (name "Net-(U1-HOSC_OUT)") (class "Default")
      (node (ref "C14") (pin "2") (pinfunction "2_2") (pintype "passive"))
      (node (ref "U1") (pin "52") (pinfunction "HOSC_OUT_52") (pintype "passive"))
      (node (ref "X1") (pin "3") (pinfunction "GND_3") (pintype "power_in"))
    )
    (net (code "84") (name "Net-(U2-FB1)") (class "Default")
      (node (ref "C7") (pin "2") (pinfunction "2_2") (pintype "passive"))
      (node (ref "R4") (pin "1") (pinfunction "1_1") (pintype "passive"))
      (node (ref "R6") (pin "1") (pinfunction "1_1") (pintype "passive"))
      (node (ref "U2") (pin "14") (pinfunction "FB1_14") (pintype "passive"))
    )
    (net (code "85") (name "Net-(U2-FB2)") (class "Default")
      (node (ref "C11") (pin "2") (pinfunction "2_2") (pintype "passive"))
      (node (ref "R7") (pin "2") (pinfunction "2_2") (pintype "passive"))
      (node (ref "R8") (pin "1") (pinfunction "1_1") (pintype "passive"))
      (node (ref "U2") (pin "3") (pinfunction "FB2_3") (pintype "passive"))
    )
    (net (code "86") (name "Net-(U2-FB3)") (class "Default")
      (node (ref "C4") (pin "2") (pinfunction "2_2") (pintype "passive"))
      (node (ref "R3") (pin "1") (pinfunction "1_1") (pintype "passive"))
      (node (ref "R5") (pin "1") (pinfunction "1_1") (pintype "passive"))
      (node (ref "U2") (pin "2") (pinfunction "FB3_2") (pintype "passive"))
    )
    (net (code "87") (name "Net-(U2-LX1)") (class "Default")
      (node (ref "L2") (pin "1") (pinfunction "1_1") (pintype "passive"))
      (node (ref "U2") (pin "11") (pinfunction "LX1_11") (pintype "passive"))
    )
    (net (code "88") (name "Net-(U2-LX2)") (class "Default")
      (node (ref "L3") (pin "2") (pinfunction "2_2") (pintype "passive"))
      (node (ref "U2") (pin "6") (pinfunction "LX2_6") (pintype "passive"))
    )
    (net (code "89") (name "Net-(U2-LX3)") (class "Default")
      (node (ref "L1") (pin "2") (pinfunction "2_2") (pintype "passive"))
      (node (ref "U2") (pin "20") (pinfunction "LX3_20") (pintype "passive"))
    )
    (net (code "90") (name "Net-(U3-EN)") (class "Default")
      (node (ref "R10") (pin "2") (pinfunction "2_2") (pintype "passive"))
      (node (ref "R9") (pin "2") (pinfunction "2_2") (pintype "passive"))
      (node (ref "U3") (pin "4") (pinfunction "EN_4") (pintype "passive"))
    )
    (net (code "91") (name "VCC_1V1") (class "Default")
      (node (ref "C10") (pin "2") (pinfunction "2_2") (pintype "passive"))
      (node (ref "C11") (pin "1") (pinfunction "1_1") (pintype "passive"))
      (node (ref "C26") (pin "2") (pinfunction "2_2") (pintype "passive"))
      (node (ref "C27") (pin "2") (pinfunction "2_2") (pintype "passive"))
      (node (ref "C28") (pin "2") (pinfunction "2_2") (pintype "passive"))
      (node (ref "L3") (pin "1") (pinfunction "1_1") (pintype "passive"))
      (node (ref "R7") (pin "1") (pinfunction "1_1") (pintype "passive"))
      (node (ref "U1") (pin "22") (pinfunction "VDD_CORE_22") (pintype "passive"))
      (node (ref "U1") (pin "35") (pinfunction "VDD_CORE_35") (pintype "passive"))
      (node (ref "U1") (pin "71") (pinfunction "VDD_CORE_71") (pintype "passive"))
    )
    (net (code "92") (name "VCC_2V5") (class "Default")
      (node (ref "C20") (pin "2") (pinfunction "2_2") (pintype "passive"))
      (node (ref "C24") (pin "2") (pinfunction "2_2") (pintype "passive"))
      (node (ref "C25") (pin "2") (pinfunction "2_2") (pintype "passive"))
      (node (ref "C7") (pin "1") (pinfunction "1_1") (pintype "passive"))
      (node (ref "C8") (pin "1") (pinfunction "1_1") (pintype "passive"))
      (node (ref "L2") (pin "2") (pinfunction "2_2") (pintype "passive"))
      (node (ref "R13") (pin "2") (pinfunction "2_2") (pintype "passive"))
      (node (ref "R6") (pin "2") (pinfunction "2_2") (pintype "passive"))
      (node (ref "U1") (pin "30") (pinfunction "VCC_DRAM_30") (pintype "passive"))
      (node (ref "U1") (pin "31") (pinfunction "VCC_DRAM_31") (pintype "passive"))
      (node (ref "U1") (pin "32") (pinfunction "VCC_DRAM_32") (pintype "passive"))
      (node (ref "U1") (pin "34") (pinfunction "VCC_DRAM_34") (pintype "passive"))
      (node (ref "U1") (pin "36") (pinfunction "VCC_DRAM_36") (pintype "passive"))
    )
    (net (code "93") (name "VCC_2V8") (class "Default")
      (node (ref "C35") (pin "2") (pinfunction "2_2") (pintype "passive"))
      (node (ref "CN2") (pin "21") (pinfunction "21_21") (pintype "passive"))
      (node (ref "JP3") (pin "2") (pintype "power_in"))
      (node (ref "U6") (pin "2") (pinfunction "VOUT_2") (pintype "power_in"))
    )
    (net (code "94") (name "VCC_3V3") (class "Default")
      (node (ref "C16") (pin "2") (pinfunction "2_2") (pintype "passive"))
      (node (ref "C17") (pin "2") (pinfunction "2_2") (pintype "passive"))
      (node (ref "C18") (pin "2") (pinfunction "2_2") (pintype "passive"))
      (node (ref "C23") (pin "2") (pinfunction "2_2") (pintype "passive"))
      (node (ref "C3") (pin "1") (pinfunction "1_1") (pintype "passive"))
      (node (ref "C30") (pin "1") (pinfunction "1_1") (pintype "passive"))
      (node (ref "C31") (pin "2") (pinfunction "2_2") (pintype "passive"))
      (node (ref "C32") (pin "2") (pinfunction "2_2") (pintype "passive"))
      (node (ref "C34") (pin "2") (pinfunction "2_2") (pintype "passive"))
      (node (ref "C36") (pin "2") (pinfunction "2_2") (pintype "passive"))
      (node (ref "C4") (pin "1") (pinfunction "1_1") (pintype "passive"))
      (node (ref "CN1") (pin "31") (pinfunction "DISP_31") (pintype "passive"))
      (node (ref "CN1") (pin "4") (pinfunction "VCC_4") (pintype "passive"))
      (node (ref "CN2") (pin "14") (pinfunction "14_14") (pintype "passive"))
      (node (ref "J1") (pin "18") (pinfunction "18_18") (pintype "passive"))
      (node (ref "J2") (pin "38") (pinfunction "38_38") (pintype "passive"))
      (node (ref "J2") (pin "4") (pinfunction "4_4") (pintype "passive"))
      (node (ref "J3") (pin "2") (pinfunction "2_2") (pintype "passive"))
      (node (ref "J3") (pin "39") (pinfunction "39_39") (pintype "passive"))
      (node (ref "L1") (pin "1") (pinfunction "1_1") (pintype "passive"))
      (node (ref "MicroSD1") (pin "4") (pinfunction "VDD_4") (pintype "power_in"))
      (node (ref "R12") (pin "2") (pinfunction "2_2") (pintype "passive"))
      (node (ref "R14") (pin "2") (pinfunction "2_2") (pintype "passive"))
      (node (ref "R17") (pin "2") (pinfunction "2_2") (pintype "passive"))
      (node (ref "R18") (pin "2") (pinfunction "2_2") (pintype "passive"))
      (node (ref "R3") (pin "2") (pinfunction "2_2") (pintype "passive"))
      (node (ref "U1") (pin "20") (pinfunction "VCC_IO_20") (pintype "passive"))
      (node (ref "U1") (pin "4") (pinfunction "HPVCC_4") (pintype "passive"))
      (node (ref "U1") (pin "5") (pinfunction "VCC_IO_5") (pintype "passive"))
      (node (ref "U1") (pin "50") (pinfunction "VCC_IO_50") (pintype "passive"))
      (node (ref "U1") (pin "67") (pinfunction "VCC_USB_67") (pintype "passive"))
      (node (ref "U4") (pin "3") (pinfunction "WP_3") (pintype "power_in"))
      (node (ref "U4") (pin "7") (pinfunction "Hold_7") (pintype "power_in"))
      (node (ref "U4") (pin "8") (pinfunction "VCC_8") (pintype "power_in"))
      (node (ref "U5") (pin "3") (pinfunction "VIN_3") (pintype "power_in"))
      (node (ref "U6") (pin "3") (pinfunction "VIN_3") (pintype "power_in"))
      (node (ref "U7") (pin "3") (pinfunction "VIN_3") (pintype "power_in"))
    )
    (net (code "95") (name "VCC_TV") (class "Default")
      (node (ref "C19") (pin "2") (pinfunction "2_2") (pintype "passive"))
      (node (ref "R12") (pin "1") (pinfunction "1_1") (pintype "passive"))
      (node (ref "U1") (pin "73") (pinfunction "TV_VCC_73") (pintype "passive"))
    )
    (net (code "96") (name "unconnected-(CN1-NC-Pad35)") (class "Default")
      (node (ref "CN1") (pin "35") (pinfunction "NC_35") (pintype "passive+no_connect"))
    )
    (net (code "97") (name "unconnected-(CN2-Pad1)") (class "Default")
      (node (ref "CN2") (pin "1") (pinfunction "1_1") (pintype "passive+no_connect"))
    )
    (net (code "98") (name "unconnected-(CN2-Pad2)") (class "Default")
      (node (ref "CN2") (pin "2") (pinfunction "2_2") (pintype "passive+no_connect"))
    )
    (net (code "99") (name "unconnected-(CN2-Pad24)") (class "Default")
      (node (ref "CN2") (pin "24") (pinfunction "24_24") (pintype "passive+no_connect"))
    )
    (net (code "100") (name "unconnected-(MicroUSB-DIP1-ID-Pad4)") (class "Default")
      (node (ref "MicroUSB-DIP1") (pin "4") (pinfunction "ID_4") (pintype "passive+no_connect"))
    )
  )
)
